# Axon_revA.net
KiCad netlist of a schematic drawn in EAGLE
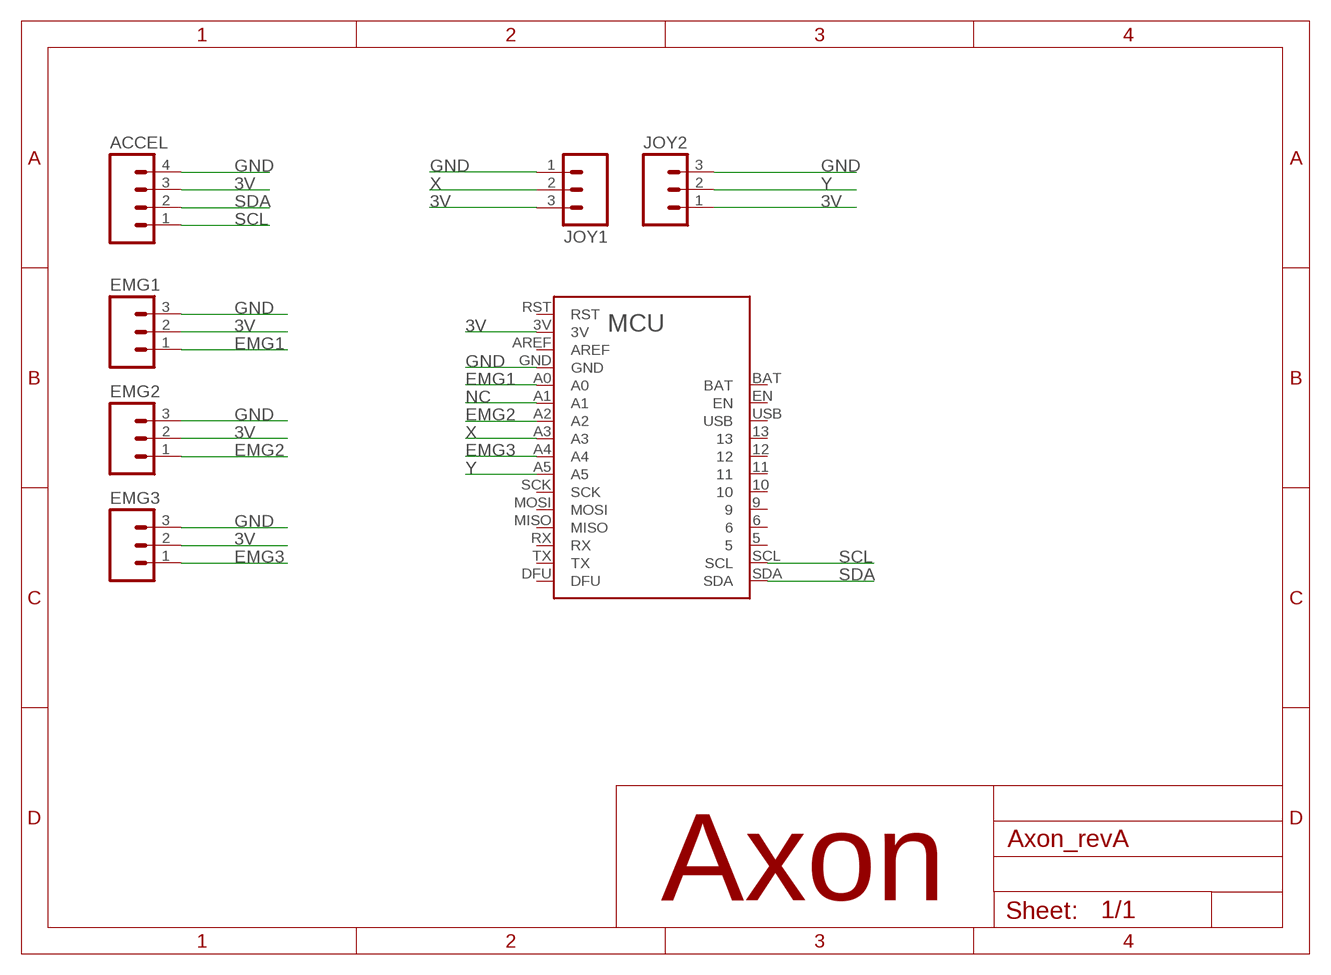
[diagram p0: schematic, sheet 1]

(export (version "E")
  (design (tool "Eeschema 10.0.6"))
  (components
    (comp (ref "ACCEL")
      (value "M04POLAR")
      (footprint "eagle-import:MOLEX-1X4")
      (libsource (lib "eagle-import") (part "M04POLAR"))
    )
    (comp (ref "EMG1")
      (value "M03POLAR")
      (footprint "eagle-import:MOLEX-1X3")
      (libsource (lib "eagle-import") (part "M03POLAR"))
    )
    (comp (ref "EMG2")
      (value "M03POLAR")
      (footprint "eagle-import:MOLEX-1X3")
      (libsource (lib "eagle-import") (part "M03POLAR"))
    )
    (comp (ref "EMG3")
      (value "M03POLAR")
      (footprint "eagle-import:MOLEX-1X3")
      (libsource (lib "eagle-import") (part "M03POLAR"))
    )
    (comp (ref "JOY1")
      (value "M03PTH")
      (footprint "eagle-import:1X03")
      (libsource (lib "eagle-import") (part "M03PTH"))
    )
    (comp (ref "JOY2")
      (value "M03PTH")
      (footprint "eagle-import:1X03")
      (libsource (lib "eagle-import") (part "M03PTH"))
    )
    (comp (ref "MCU")
      (value "BLUEFRUIT")
      (footprint "eagle-import:BLUEFRUIT")
      (libsource (lib "eagle-import") (part "BLUEFRUIT"))
    )
  )
  (nets
    (net (code "1") (name "/3V") (class "Default")
      (node (ref "ACCEL") (pin "3") (pinfunction "3_3") (pintype "passive"))
      (node (ref "EMG1") (pin "2") (pinfunction "2_2") (pintype "passive"))
      (node (ref "EMG2") (pin "2") (pinfunction "2_2") (pintype "passive"))
      (node (ref "EMG3") (pin "2") (pinfunction "2_2") (pintype "passive"))
      (node (ref "JOY1") (pin "3") (pinfunction "3_3") (pintype "passive"))
      (node (ref "JOY2") (pin "1") (pinfunction "1_1") (pintype "passive"))
      (node (ref "MCU") (pin "3V") (pinfunction "3V_3V") (pintype "power_in"))
    )
    (net (code "2") (name "/EMG1") (class "Default")
      (node (ref "EMG1") (pin "1") (pinfunction "1_1") (pintype "passive"))
      (node (ref "MCU") (pin "A0") (pinfunction "A0_A0") (pintype "bidirectional"))
    )
    (net (code "3") (name "/EMG2") (class "Default")
      (node (ref "EMG2") (pin "1") (pinfunction "1_1") (pintype "passive"))
      (node (ref "MCU") (pin "A2") (pinfunction "A2_A2") (pintype "bidirectional"))
    )
    (net (code "4") (name "/EMG3") (class "Default")
      (node (ref "EMG3") (pin "1") (pinfunction "1_1") (pintype "passive"))
      (node (ref "MCU") (pin "A4") (pinfunction "A4_A4") (pintype "bidirectional"))
    )
    (net (code "5") (name "/GND") (class "Default")
      (node (ref "ACCEL") (pin "4") (pinfunction "4_4") (pintype "passive"))
      (node (ref "EMG1") (pin "3") (pinfunction "3_3") (pintype "passive"))
      (node (ref "EMG2") (pin "3") (pinfunction "3_3") (pintype "passive"))
      (node (ref "EMG3") (pin "3") (pinfunction "3_3") (pintype "passive"))
      (node (ref "JOY1") (pin "1") (pinfunction "1_1") (pintype "passive"))
      (node (ref "JOY2") (pin "3") (pinfunction "3_3") (pintype "passive"))
      (node (ref "MCU") (pin "GND") (pinfunction "GND_GND") (pintype "power_in"))
    )
    (net (code "6") (name "/NC") (class "Default")
      (node (ref "MCU") (pin "A1") (pinfunction "A1_A1") (pintype "bidirectional"))
    )
    (net (code "7") (name "/SCL") (class "Default")
      (node (ref "ACCEL") (pin "1") (pinfunction "1_1") (pintype "passive"))
      (node (ref "MCU") (pin "SCL") (pinfunction "SCL_SCL") (pintype "bidirectional"))
    )
    (net (code "8") (name "/SDA") (class "Default")
      (node (ref "ACCEL") (pin "2") (pinfunction "2_2") (pintype "passive"))
      (node (ref "MCU") (pin "SDA") (pinfunction "SDA_SDA") (pintype "bidirectional"))
    )
    (net (code "9") (name "/X") (class "Default")
      (node (ref "JOY1") (pin "2") (pinfunction "2_2") (pintype "passive"))
      (node (ref "MCU") (pin "A3") (pinfunction "A3_A3") (pintype "bidirectional"))
    )
    (net (code "10") (name "/Y") (class "Default")
      (node (ref "JOY2") (pin "2") (pinfunction "2_2") (pintype "passive"))
      (node (ref "MCU") (pin "A5") (pinfunction "A5_A5") (pintype "bidirectional"))
    )
    (net (code "11") (name "unconnected-(MCU-Pad5)") (class "Default")
      (node (ref "MCU") (pin "5") (pinfunction "5_5") (pintype "bidirectional"))
    )
    (net (code "12") (name "unconnected-(MCU-Pad6)") (class "Default")
      (node (ref "MCU") (pin "6") (pinfunction "6_6") (pintype "bidirectional"))
    )
    (net (code "13") (name "unconnected-(MCU-Pad9)") (class "Default")
      (node (ref "MCU") (pin "9") (pinfunction "9_9") (pintype "bidirectional"))
    )
    (net (code "14") (name "unconnected-(MCU-Pad10)") (class "Default")
      (node (ref "MCU") (pin "10") (pinfunction "10_10") (pintype "bidirectional"))
    )
    (net (code "15") (name "unconnected-(MCU-Pad11)") (class "Default")
      (node (ref "MCU") (pin "11") (pinfunction "11_11") (pintype "bidirectional"))
    )
    (net (code "16") (name "unconnected-(MCU-Pad12)") (class "Default")
      (node (ref "MCU") (pin "12") (pinfunction "12_12") (pintype "bidirectional"))
    )
    (net (code "17") (name "unconnected-(MCU-Pad13)") (class "Default")
      (node (ref "MCU") (pin "13") (pinfunction "13_13") (pintype "bidirectional"))
    )
    (net (code "18") (name "unconnected-(MCU-PadAREF)") (class "Default")
      (node (ref "MCU") (pin "AREF") (pinfunction "AREF_AREF") (pintype "bidirectional"))
    )
    (net (code "19") (name "unconnected-(MCU-PadBAT)") (class "Default")
      (node (ref "MCU") (pin "BAT") (pinfunction "BAT_BAT") (pintype "bidirectional"))
    )
    (net (code "20") (name "unconnected-(MCU-PadDFU)") (class "Default")
      (node (ref "MCU") (pin "DFU") (pinfunction "DFU_DFU") (pintype "bidirectional"))
    )
    (net (code "21") (name "unconnected-(MCU-PadEN)") (class "Default")
      (node (ref "MCU") (pin "EN") (pinfunction "EN_EN") (pintype "bidirectional"))
    )
    (net (code "22") (name "unconnected-(MCU-PadMISO)") (class "Default")
      (node (ref "MCU") (pin "MISO") (pinfunction "MISO_MISO") (pintype "bidirectional"))
    )
    (net (code "23") (name "unconnected-(MCU-PadMOSI)") (class "Default")
      (node (ref "MCU") (pin "MOSI") (pinfunction "MOSI_MOSI") (pintype "bidirectional"))
    )
    (net (code "24") (name "unconnected-(MCU-PadRST)") (class "Default")
      (node (ref "MCU") (pin "RST") (pinfunction "RST_RST") (pintype "bidirectional"))
    )
    (net (code "25") (name "unconnected-(MCU-PadRX)") (class "Default")
      (node (ref "MCU") (pin "RX") (pinfunction "RX_RX") (pintype "bidirectional"))
    )
    (net (code "26") (name "unconnected-(MCU-PadSCK)") (class "Default")
      (node (ref "MCU") (pin "SCK") (pinfunction "SCK_SCK") (pintype "bidirectional"))
    )
    (net (code "27") (name "unconnected-(MCU-PadTX)") (class "Default")
      (node (ref "MCU") (pin "TX") (pinfunction "TX_TX") (pintype "bidirectional"))
    )
    (net (code "28") (name "unconnected-(MCU-PadUSB)") (class "Default")
      (node (ref "MCU") (pin "USB") (pinfunction "USB_USB") (pintype "bidirectional"))
    )
  )
)
